# I-Bus_Adapter_with_Power_Supply.net
KiCad netlist of a schematic drawn in EAGLE
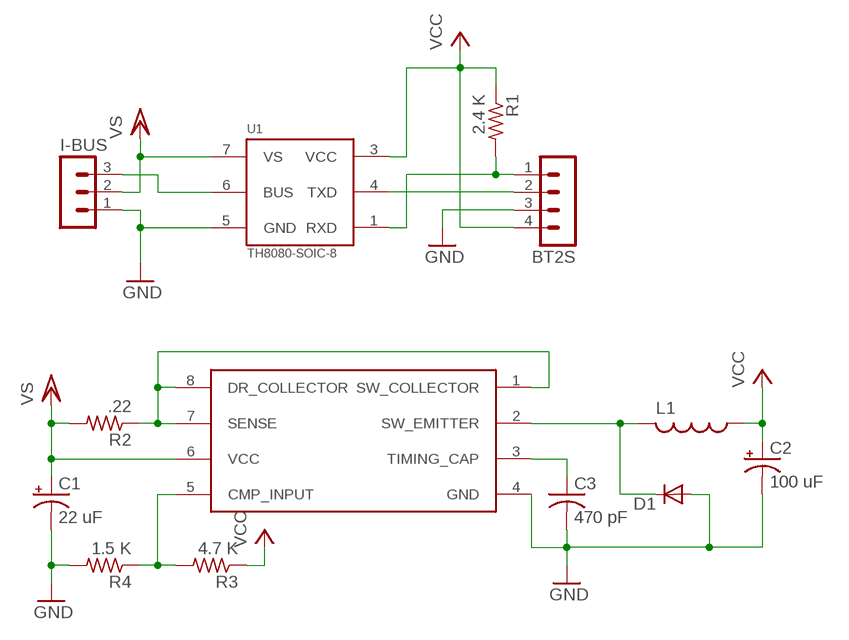
[diagram p0: schematic, sheet 1]

(export (version "E")
  (design (tool "Eeschema 10.0.6"))
  (components
    (comp (ref "BT2S")
      (value "MA04-1")
      (footprint "eagle-import:MA04-1")
      (libsource (lib "eagle-import") (part "MA04-1"))
    )
    (comp (ref "C1")
      (value "22 uF")
      (footprint "eagle-import:E1,8-4")
      (libsource (lib "eagle-import") (part "CPOL-USE1.8-4"))
    )
    (comp (ref "C2")
      (value "100 uF")
      (footprint "eagle-import:E1,8-4")
      (libsource (lib "eagle-import") (part "CPOL-USE1.8-4"))
    )
    (comp (ref "C3")
      (value "470 pF")
      (footprint "eagle-import:C0603K")
      (libsource (lib "eagle-import") (part "C-USC0603K"))
    )
    (comp (ref "D1")
      (value "DIODE-D-2.5")
      (footprint "eagle-import:D-2.5")
      (libsource (lib "eagle-import") (part "DIODE-D-2.5"))
    )
    (comp (ref "I-BUS")
      (value "MA03-1")
      (footprint "eagle-import:MA03-1")
      (libsource (lib "eagle-import") (part "MA03-1"))
    )
    (comp (ref "L1")
      (value "L-US0207/2V")
      (footprint "eagle-import:0207_2V")
      (libsource (lib "eagle-import") (part "L-US0207/2V"))
    )
    (comp (ref "R1")
      (value "2.4 K")
      (footprint "eagle-import:R1206")
      (libsource (lib "eagle-import") (part "R-US_R1206"))
    )
    (comp (ref "R2")
      (value ".22")
      (footprint "eagle-import:R1206")
      (libsource (lib "eagle-import") (part "R-US_R1206"))
    )
    (comp (ref "R3")
      (value "4.7 K")
      (footprint "eagle-import:R2012")
      (libsource (lib "eagle-import") (part "R-US_R2012"))
    )
    (comp (ref "R4")
      (value "1.5 K")
      (footprint "eagle-import:R2012")
      (libsource (lib "eagle-import") (part "R-US_R2012"))
    )
    (comp (ref "U1")
      (value "TH8080-SOIC-8")
      (footprint "eagle-import:SO-8")
      (libsource (lib "eagle-import") (part "TH8080-SOIC-8"))
    )
    (comp (ref "U2")
      (value "MC34063-SOIC-8")
      (footprint "eagle-import:SO-8")
      (libsource (lib "eagle-import") (part "MC34063-SOIC-8"))
    )
  )
  (nets
    (net (code "1") (name "GND") (class "Default")
      (node (ref "BT2S") (pin "3") (pinfunction "3_3") (pintype "passive"))
      (node (ref "C1") (pin "-") (pinfunction "-_-") (pintype "passive"))
      (node (ref "C2") (pin "-") (pinfunction "-_-") (pintype "passive"))
      (node (ref "C3") (pin "2") (pinfunction "2_2") (pintype "passive"))
      (node (ref "D1") (pin "A") (pinfunction "A_A") (pintype "passive"))
      (node (ref "I-BUS") (pin "1") (pinfunction "1_1") (pintype "passive"))
      (node (ref "R4") (pin "2") (pinfunction "2_2") (pintype "passive"))
      (node (ref "U1") (pin "5") (pinfunction "GND_5") (pintype "power_in"))
      (node (ref "U2") (pin "4") (pinfunction "GND_4") (pintype "power_in"))
    )
    (net (code "2") (name "Net-(U1-BUS)") (class "Default")
      (node (ref "I-BUS") (pin "3") (pinfunction "3_3") (pintype "passive"))
      (node (ref "U1") (pin "6") (pinfunction "BUS_6") (pintype "bidirectional"))
    )
    (net (code "3") (name "Net-(U1-RXD)") (class "Default")
      (node (ref "BT2S") (pin "1") (pinfunction "1_1") (pintype "passive"))
      (node (ref "R1") (pin "2") (pinfunction "2_2") (pintype "passive"))
      (node (ref "U1") (pin "1") (pinfunction "RXD_1") (pintype "output"))
    )
    (net (code "4") (name "Net-(U1-TXD)") (class "Default")
      (node (ref "BT2S") (pin "2") (pinfunction "2_2") (pintype "passive"))
      (node (ref "U1") (pin "4") (pinfunction "TXD_4") (pintype "input"))
    )
    (net (code "5") (name "Net-(U2-CMP_INPUT)") (class "Default")
      (node (ref "R3") (pin "2") (pinfunction "2_2") (pintype "passive"))
      (node (ref "R4") (pin "1") (pinfunction "1_1") (pintype "passive"))
      (node (ref "U2") (pin "5") (pinfunction "CMP_INPUT_5") (pintype "bidirectional"))
    )
    (net (code "6") (name "Net-(U2-DR_COLLECTOR)") (class "Default")
      (node (ref "R2") (pin "1") (pinfunction "1_1") (pintype "passive"))
      (node (ref "U2") (pin "1") (pinfunction "SW_COLLECTOR_1") (pintype "bidirectional"))
      (node (ref "U2") (pin "7") (pinfunction "SENSE_7") (pintype "bidirectional"))
      (node (ref "U2") (pin "8") (pinfunction "DR_COLLECTOR_8") (pintype "bidirectional"))
    )
    (net (code "7") (name "Net-(U2-SW_EMITTER)") (class "Default")
      (node (ref "D1") (pin "C") (pinfunction "C_C") (pintype "passive"))
      (node (ref "L1") (pin "2") (pinfunction "2_2") (pintype "passive"))
      (node (ref "U2") (pin "2") (pinfunction "SW_EMITTER_2") (pintype "bidirectional"))
    )
    (net (code "8") (name "Net-(U2-TIMING_CAP)") (class "Default")
      (node (ref "C3") (pin "1") (pinfunction "1_1") (pintype "passive"))
      (node (ref "U2") (pin "3") (pinfunction "TIMING_CAP_3") (pintype "bidirectional"))
    )
    (net (code "9") (name "VCC") (class "Default")
      (node (ref "BT2S") (pin "4") (pinfunction "4_4") (pintype "passive"))
      (node (ref "C2") (pin "+") (pinfunction "+_+") (pintype "passive"))
      (node (ref "L1") (pin "1") (pinfunction "1_1") (pintype "passive"))
      (node (ref "R1") (pin "1") (pinfunction "1_1") (pintype "passive"))
      (node (ref "R3") (pin "1") (pinfunction "1_1") (pintype "passive"))
      (node (ref "U1") (pin "3") (pinfunction "VCC_3") (pintype "power_in"))
    )
    (net (code "10") (name "VS") (class "Default")
      (node (ref "C1") (pin "+") (pinfunction "+_+") (pintype "passive"))
      (node (ref "I-BUS") (pin "2") (pinfunction "2_2") (pintype "passive"))
      (node (ref "R2") (pin "2") (pinfunction "2_2") (pintype "passive"))
      (node (ref "U1") (pin "7") (pinfunction "VS_7") (pintype "power_in"))
      (node (ref "U2") (pin "6") (pinfunction "VCC_6") (pintype "power_in"))
    )
  )
)
